# stm32f103.net
KiCad netlist of a schematic drawn in Altium Designer
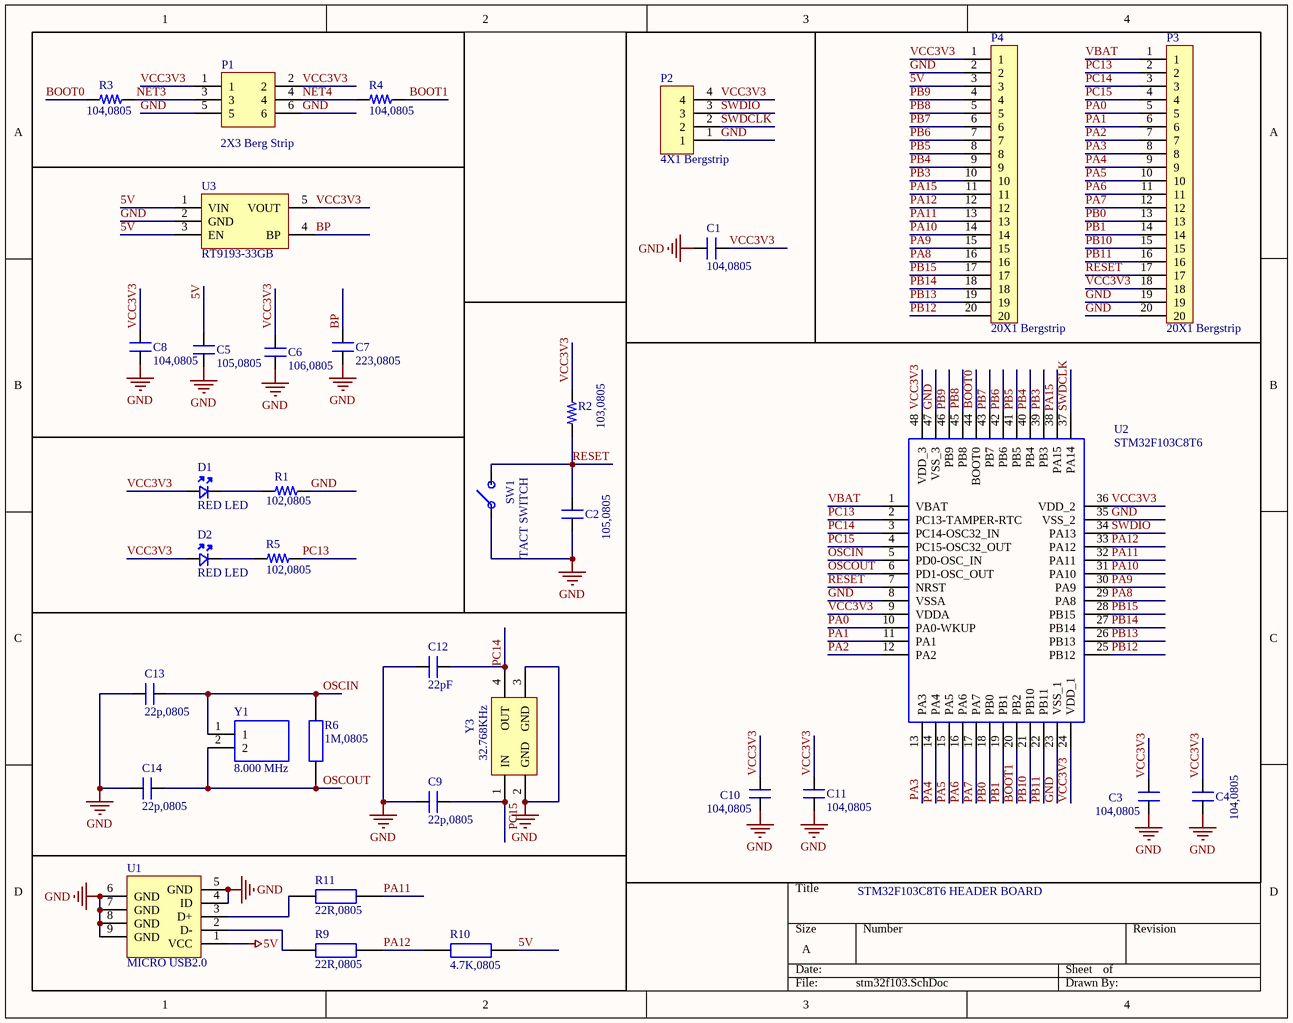
[diagram p0: stm32f103.SchDoc]

(export (version "E")
  (design (tool "Eeschema 10.0.6"))
  (components
    (comp (ref "C1")
      (value "104,0805")
      (footprint "CAP_0805")
      (description "0.1µF ±5% 50V Ceramic Capacitor X7R 0805 (2012 Metric)")
      (fields
        (field (name "MANUFACTURER") "KEMET")
        (field (name "MANUFACTURING PART NUMBER") "C0805C104J5RACTU")
      )
      (libsource (lib "STM_SCH_LIB") (part "CAP_0.1uF-50V-5%-0805"))
    )
    (comp (ref "C2")
      (value "105,0805")
      (footprint "CAP_0805")
      (description "1µF ±5% 50V Ceramic Capacitor X7R 0805 (2012 Metric)")
      (fields
        (field (name "MANUFACTURER") "Yageo")
        (field (name "MANUFACTURING PART NUMBER") "CC0805JKX7R9BB105")
      )
      (libsource (lib "STM_SCH_LIB") (part "CAP_1uF-50V-5%-0805"))
    )
    (comp (ref "C3")
      (value "104,0805")
      (footprint "CAP_0805")
      (description "0.1µF ±5% 50V Ceramic Capacitor X7R 0805 (2012 Metric)")
      (fields
        (field (name "MANUFACTURER") "KEMET")
        (field (name "MANUFACTURING PART NUMBER") "C0805C104J5RACTU")
      )
      (libsource (lib "STM_SCH_LIB") (part "CAP_0.1uF-50V-5%-0805"))
    )
    (comp (ref "C4")
      (value "104,0805")
      (footprint "CAP_0805")
      (description "0.1µF ±5% 50V Ceramic Capacitor X7R 0805 (2012 Metric)")
      (fields
        (field (name "MANUFACTURER") "KEMET")
        (field (name "MANUFACTURING PART NUMBER") "C0805C104J5RACTU")
      )
      (libsource (lib "STM_SCH_LIB") (part "CAP_0.1uF-50V-5%-0805"))
    )
    (comp (ref "C5")
      (value "105,0805")
      (footprint "CAP_0805")
      (description "1µF ±5% 50V Ceramic Capacitor X7R 0805 (2012 Metric)")
      (fields
        (field (name "MANUFACTURER") "Yageo")
        (field (name "MANUFACTURING PART NUMBER") "CC0805JKX7R9BB105")
      )
      (libsource (lib "STM_SCH_LIB") (part "CAP_1uF-50V-5%-0805"))
    )
    (comp (ref "C6")
      (value "106,0805")
      (footprint "CAP_0805")
      (description "10µF ±5% 50V Ceramic Capacitor X7R 0805 (2012 Metric)")
      (fields
        (field (name "MANUFACTURER") "Yageo")
        (field (name "MANUFACTURING PART NUMBER") "CC0805JKX7R9BB105")
      )
      (libsource (lib "STM_SCH_LIB") (part "CAP_1uF-50V-5%-0805"))
    )
    (comp (ref "C7")
      (value "223,0805")
      (footprint "CAP_0805")
      (description "0.1µF ±5% 50V Ceramic Capacitor X7R 0805 (2012 Metric)")
      (fields
        (field (name "MANUFACTURER") "KEMET")
        (field (name "MANUFACTURING PART NUMBER") "C0805C104J5RACTU")
      )
      (libsource (lib "STM_SCH_LIB") (part "CAP_0.1uF-50V-5%-0805"))
    )
    (comp (ref "C8")
      (value "104,0805")
      (footprint "CAP_0805")
      (description "0.1µF ±5% 50V Ceramic Capacitor X7R 0805 (2012 Metric)")
      (fields
        (field (name "MANUFACTURER") "KEMET")
        (field (name "MANUFACTURING PART NUMBER") "C0805C104J5RACTU")
      )
      (libsource (lib "STM_SCH_LIB") (part "CAP_0.1uF-50V-5%-0805"))
    )
    (comp (ref "C9")
      (value "22p,0805")
      (footprint "CAP_0805")
      (description "22pF ±5% 50V Ceramic Capacitor C0G, NP0 0805 (2012 Metric)")
      (fields
        (field (name "MANUFACTURER") "KEMET")
        (field (name "MANUFACTURER PART NUMBER") "C0805C220J5GACTU")
      )
      (libsource (lib "STM_SCH_LIB") (part "CAP_22pF-50V-5%-0805"))
    )
    (comp (ref "C10")
      (value "104,0805")
      (footprint "CAP_0805")
      (description "0.1µF ±5% 50V Ceramic Capacitor X7R 0805 (2012 Metric)")
      (fields
        (field (name "MANUFACTURER") "KEMET")
        (field (name "MANUFACTURING PART NUMBER") "C0805C104J5RACTU")
      )
      (libsource (lib "STM_SCH_LIB") (part "CAP_0.1uF-50V-5%-0805"))
    )
    (comp (ref "C11")
      (value "104,0805")
      (footprint "CAP_0805")
      (description "0.1µF ±5% 50V Ceramic Capacitor X7R 0805 (2012 Metric)")
      (fields
        (field (name "MANUFACTURER") "KEMET")
        (field (name "MANUFACTURING PART NUMBER") "C0805C104J5RACTU")
      )
      (libsource (lib "STM_SCH_LIB") (part "CAP_0.1uF-50V-5%-0805"))
    )
    (comp (ref "C12")
      (value "22pF")
      (footprint "CAP_0805")
      (description "22pF ±5% 50V Ceramic Capacitor C0G, NP0 0805 (2012 Metric)")
      (fields
        (field (name "MANUFACTURER") "KEMET")
        (field (name "MANUFACTURER PART NUMBER") "C0805C220J5GACTU")
      )
      (libsource (lib "STM_SCH_LIB") (part "CAP_22pF-50V-5%-0805"))
    )
    (comp (ref "C13")
      (value "22p,0805")
      (footprint "CAP_0805")
      (description "22pF ±5% 50V Ceramic Capacitor C0G, NP0 0805 (2012 Metric)")
      (fields
        (field (name "MANUFACTURER") "KEMET")
        (field (name "MANUFACTURER PART NUMBER") "C0805C220J5GACTU")
      )
      (libsource (lib "STM_SCH_LIB") (part "CAP_22pF-50V-5%-0805"))
    )
    (comp (ref "C14")
      (value "22p,0805")
      (footprint "CAP_0805")
      (description "22pF ±5% 50V Ceramic Capacitor C0G, NP0 0805 (2012 Metric)")
      (fields
        (field (name "MANUFACTURER") "KEMET")
        (field (name "MANUFACTURER PART NUMBER") "C0805C220J5GACTU")
      )
      (libsource (lib "STM_SCH_LIB") (part "CAP_22pF-50V-5%-0805"))
    )
    (comp (ref "D1")
      (value "RED LED")
      (footprint "LED_0805")
      (description "Red 621nm LED Indication - Discrete 2V 0805 (2012 Metric)")
      (fields
        (field (name "MANUFACTURER") "Lite-On Inc.")
        (field (name "MANUFACTURER PART NUMBER") "LTST-C170EKT")
      )
      (libsource (lib "STM_SCH_LIB") (part "LED-RED_10mA-0805"))
    )
    (comp (ref "D2")
      (value "RED LED")
      (footprint "LED_0805")
      (description "Red 621nm LED Indication - Discrete 2V 0805 (2012 Metric)")
      (fields
        (field (name "MANUFACTURER") "Lite-On Inc.")
        (field (name "MANUFACTURER PART NUMBER") "LTST-C170EKT")
      )
      (libsource (lib "STM_SCH_LIB") (part "LED-RED_10mA-0805"))
    )
    (comp (ref "P1")
      (value "2X3 Berg Strip")
      (footprint "CON6_100_59D78_TH_ST_Duplicate")
      (description "6 pin, 2 row, 2.54mm pitch bergstrip")
      (fields (field (name "MANUFACTURER") "NA"))
      (libsource (lib "STM_SCH_LIB") (part "CON-BS-PLG_2X3-100-TH-ST"))
    )
    (comp (ref "P2")
      (value "4X1 Bergstrip")
      (footprint "CON4_100_40D72_TH_ST_MALE")
      (description "4 pin, 1 row, 2.54mm pitch bergstrip")
      (fields (field (name "MANUFACTURER") "NA"))
      (libsource (lib "STM_SCH_LIB") (part "CON-BS-PLG_4X1-100-TH-ST"))
    )
    (comp (ref "P3")
      (value "20X1 Bergstrip")
      (footprint "CON20_100_40D72_TH_ST")
      (description "20 pin, 1 row, 2.54mm pitch bergstrip")
      (fields (field (name "MANUFACTURER") "NA"))
      (libsource (lib "STM_SCH_LIB") (part "CON-BS-PLG_20X1-100-TH-ST"))
    )
    (comp (ref "P4")
      (value "20X1 Bergstrip")
      (footprint "CON20_100_40D72_TH_ST")
      (description "20 pin, 1 row, 2.54mm pitch bergstrip")
      (fields (field (name "MANUFACTURER") "NA"))
      (libsource (lib "STM_SCH_LIB") (part "CON-BS-PLG_20X1-100-TH-ST"))
    )
    (comp (ref "R1")
      (value "102,0805")
      (footprint "RES_0805")
      (description "1 kOhms ±1% 0.125W, 1/8W Chip Resistor 0805 (2012 Metric) Moisture Resistant Thick Film")
      (fields (field (name "MANUFACTURER") "垈㎵á") (field (name "MANUFACTURER PART NUMBER") "RC0805FR-071KL"))
      (libsource (lib "STM_SCH_LIB") (part "RES_1K-0.125W-1%-0805"))
    )
    (comp (ref "R2")
      (value "103,0805")
      (footprint "RES_0805")
      (description "10 kOhms ±1% 0.125W, 1/8W Chip Resistor 0805 (2012 Metric) Moisture Resistant Thick Film")
      (fields
        (field (name "MANUFACTURER") "Yageo")
        (field (name "MANUFACTURING PART NUMBER") "RC0805FR-0710KL")
      )
      (libsource (lib "STM_SCH_LIB") (part "RES_10K-0.125W-1%-0805"))
    )
    (comp (ref "R3")
      (value "104,0805")
      (footprint "RES_0805")
      (description "10 kOhms ±1% 0.125W, 1/8W Chip Resistor 0805 (2012 Metric) Moisture Resistant Thick Film")
      (fields
        (field (name "MANUFACTURER") "Yageo")
        (field (name "MANUFACTURING PART NUMBER") "RC0805FR-0710KL")
      )
      (libsource (lib "STM_SCH_LIB") (part "RES_10K-0.125W-1%-0805"))
    )
    (comp (ref "R4")
      (value "104,0805")
      (footprint "RES_0805")
      (description "10 kOhms ±1% 0.125W, 1/8W Chip Resistor 0805 (2012 Metric) Moisture Resistant Thick Film")
      (fields
        (field (name "MANUFACTURER") "Yageo")
        (field (name "MANUFACTURING PART NUMBER") "RC0805FR-0710KL")
      )
      (libsource (lib "STM_SCH_LIB") (part "RES_10K-0.125W-1%-0805"))
    )
    (comp (ref "R5")
      (value "102,0805")
      (footprint "RES_0805")
      (description "1 kOhms ±1% 0.125W, 1/8W Chip Resistor 0805 (2012 Metric) Moisture Resistant Thick Film")
      (fields (field (name "MANUFACTURER") "垈㎵á") (field (name "MANUFACTURER PART NUMBER") "RC0805FR-071KL"))
      (libsource (lib "STM_SCH_LIB") (part "RES_1K-0.125W-1%-0805"))
    )
    (comp (ref "R6")
      (value "1M,0805")
      (footprint "RESC2013X65N")
      (description "TE Connectivity CRGS Series Thick Film Anti-surge Resistor 0805 Case 1M +/-5% 0.5W +/-100ppm/C")
      (fields
        (field (name "MANUFACTURER_PART_NUMBER") "CRGS0805J1M0")
        (field (name "RS PART NUMBER") "9059767")
      )
      (libsource (lib "Res_1M_0805") (part "CRGS0805J1M0"))
    )
    (comp (ref "R9")
      (value "22R,0805")
      (footprint "RESC2013X65N")
      (description "TE Connectivity Thick Film Surface Mount Fixed Resistor 0805 Case 22 +/-5% 0.33W +/-200ppm/C")
      (fields
        (field (name "MANUFACTURER_PART_NUMBER") "CRGH0805J22R")
        (field (name "MOUSER PART NUMBER") "279-CRGH0805J22R")
      )
      (libsource (lib "Res_22R_0805") (part "CRGH0805J22R"))
    )
    (comp (ref "R10")
      (value "4.7K,0805")
      (footprint "RESC2013X65N")
      (description "RESISTOR, 0805 4.7K Ohm +/-5% 0.125 W")
      (fields
        (field (name "MANUFACTURER_PART_NUMBER") "ERJ-6GEYJ472V")
        (field (name "MOUSER PART NUMBER") "667-ERJ-6GEYJ472V")
      )
      (libsource (lib "Res_4.7_0805") (part "ERJ-6GEYJ472V"))
    )
    (comp (ref "R11")
      (value "22R,0805")
      (footprint "RESC2013X65N")
      (description "TE Connectivity Thick Film Surface Mount Fixed Resistor 0805 Case 22 +/-5% 0.33W +/-200ppm/C")
      (fields
        (field (name "MANUFACTURER_PART_NUMBER") "CRGH0805J22R")
        (field (name "MOUSER PART NUMBER") "279-CRGH0805J22R")
      )
      (libsource (lib "Res_22R_0805") (part "CRGH0805J22R"))
    )
    (comp (ref "SW1")
      (value "TACT SWITCH")
      (footprint "SW_342_SMD")
      (description "Tactile Switch SPST-NO Top Actuated Surface Mount")
      (fields (field (name "MANUFACTURER") "C&K") (field (name "MANUFACTURING PART NUMBER") "KSR223GLFG"))
      (libsource (lib "STM_SCH_LIB") (part "SW_KSR223GLFG-SMD"))
    )
    (comp (ref "U1")
      (value "MICRO USB2.0")
      (footprint "CON_10118192-0001LF_SMD")
      (description "USB - micro B USB 2.0 Receptacle Connector 5 Position Surface Mount, Right Angle")
      (fields
        (field (name "MANUFACTURER") "Amphenol ICC (FCI)")
        (field (name "MANUFACTURING PART NUMBER") "10118192-0002LF")
      )
      (libsource (lib "STM_SCH_LIB") (part "CON-USB_10118192-0002LF-SMD"))
    )
    (comp (ref "U2")
      (value "STM32F103C8T6")
      (footprint "QFP50P900X900X160-48N")
      (fields
        (field (name "MOUSER PART NUMBER") "511-STM32F103C8T6")
        (field (name "RS PART NUMBER") "0402279P")
      )
      (libsource (lib "IC_STM32F103C8T6") (part "STM32F103C8T6"))
    )
    (comp (ref "U3")
      (value "RT9193-33GB")
      (footprint "SOT23-5")
      (description "Linear Voltage Regulator IC 1 Output 300mA SOT-23-5")
      (fields (field (name "MANUFACTURER") "Richtek USA Inc."))
      (libsource (lib "STM_SCH_LIB") (part "REG_3.3V-5.5V-0.3A-SOT-23-5"))
    )
    (comp (ref "Y1")
      (value "8.000 MHz")
      (footprint "HC-49S_1")
      (description "TXC - 9B-16.000MEEJ-B - XTAL, 16.000MHZ, 18PF, HC-49S")
      (fields
        (field (name "MANUFACTURER_PART_NUMBER") "9B-16.000MEEJ-B")
        (field (name "MOUSER PART NUMBER") "717-9B-16.000MEEJ-B")
      )
      (libsource (lib "16 MHz resonator") (part "9B-16.000MEEJ-B"))
    )
    (comp (ref "Y3")
      (value "32.768KHz")
      (footprint "XTAL_MC-405 32.7680K-G3")
      (description "Crystals SMD AT XTL MHZ +/-50PPM 12.5 PF 250 T/R")
      (fields
        (field (name "MANUFACTURER") "Epson")
        (field (name "MANUFACTURING PART NUMBER") "MC-405 32.7680K-G3: ROHS")
      )
      (libsource (lib "STM_SCH_LIB") (part "XTAL_32.768KHz-MC-405 32.7680K-G3"))
    )
  )
  (nets
    (net (code "1") (name "/BOOT0") (class "Default")
      (node (ref "R3") (pin "1") (pinfunction "1_1") (pintype "passive"))
      (node (ref "U2") (pin "44") (pinfunction "BOOT0_44") (pintype "passive"))
    )
    (net (code "2") (name "/BOOT1") (class "Default")
      (node (ref "R4") (pin "2") (pinfunction "2_2") (pintype "passive"))
      (node (ref "U2") (pin "20") (pinfunction "PB2_20") (pintype "passive"))
    )
    (net (code "3") (name "/BP") (class "Default")
      (node (ref "C7") (pin "2") (pinfunction "2_2") (pintype "passive"))
      (node (ref "U3") (pin "4") (pinfunction "BP_4") (pintype "passive"))
    )
    (net (code "4") (name "/NET3") (class "Default")
      (node (ref "P1") (pin "3") (pinfunction "3_3") (pintype "passive"))
      (node (ref "R3") (pin "2") (pinfunction "2_2") (pintype "passive"))
    )
    (net (code "5") (name "/NET4") (class "Default")
      (node (ref "P1") (pin "4") (pinfunction "4_4") (pintype "passive"))
      (node (ref "R4") (pin "1") (pinfunction "1_1") (pintype "passive"))
    )
    (net (code "6") (name "/OSCIN") (class "Default")
      (node (ref "C13") (pin "2") (pinfunction "2_2") (pintype "passive"))
      (node (ref "R6") (pin "2") (pinfunction "2_2") (pintype "passive"))
      (node (ref "U2") (pin "5") (pinfunction "PD0-OSC_IN_5") (pintype "passive"))
      (node (ref "Y1") (pin "1") (pinfunction "1_1") (pintype "passive"))
    )
    (net (code "7") (name "/OSCOUT") (class "Default")
      (node (ref "C14") (pin "2") (pinfunction "2_2") (pintype "passive"))
      (node (ref "R6") (pin "1") (pinfunction "1_1") (pintype "passive"))
      (node (ref "U2") (pin "6") (pinfunction "PD1-OSC_OUT_6") (pintype "passive"))
      (node (ref "Y1") (pin "2") (pinfunction "2_2") (pintype "passive"))
    )
    (net (code "8") (name "/PA0") (class "Default")
      (node (ref "P3") (pin "5") (pinfunction "5_5") (pintype "passive"))
      (node (ref "U2") (pin "10") (pinfunction "PA0-WKUP_10") (pintype "passive"))
    )
    (net (code "9") (name "/PA1") (class "Default")
      (node (ref "P3") (pin "6") (pinfunction "6_6") (pintype "passive"))
      (node (ref "U2") (pin "11") (pinfunction "PA1_11") (pintype "passive"))
    )
    (net (code "10") (name "/PA2") (class "Default")
      (node (ref "P3") (pin "7") (pinfunction "7_7") (pintype "passive"))
      (node (ref "U2") (pin "12") (pinfunction "PA2_12") (pintype "passive"))
    )
    (net (code "11") (name "/PA3") (class "Default")
      (node (ref "P3") (pin "8") (pinfunction "8_8") (pintype "passive"))
      (node (ref "U2") (pin "13") (pinfunction "PA3_13") (pintype "passive"))
    )
    (net (code "12") (name "/PA4") (class "Default")
      (node (ref "P3") (pin "9") (pinfunction "9_9") (pintype "passive"))
      (node (ref "U2") (pin "14") (pinfunction "PA4_14") (pintype "passive"))
    )
    (net (code "13") (name "/PA5") (class "Default")
      (node (ref "P3") (pin "10") (pinfunction "10_10") (pintype "passive"))
      (node (ref "U2") (pin "15") (pinfunction "PA5_15") (pintype "passive"))
    )
    (net (code "14") (name "/PA6") (class "Default")
      (node (ref "P3") (pin "11") (pinfunction "11_11") (pintype "passive"))
      (node (ref "U2") (pin "16") (pinfunction "PA6_16") (pintype "passive"))
    )
    (net (code "15") (name "/PA7") (class "Default")
      (node (ref "P3") (pin "12") (pinfunction "12_12") (pintype "passive"))
      (node (ref "U2") (pin "17") (pinfunction "PA7_17") (pintype "passive"))
    )
    (net (code "16") (name "/PA8") (class "Default")
      (node (ref "P4") (pin "16") (pinfunction "16_16") (pintype "passive"))
      (node (ref "U2") (pin "29") (pinfunction "PA8_29") (pintype "passive"))
    )
    (net (code "17") (name "/PA9") (class "Default")
      (node (ref "P4") (pin "15") (pinfunction "15_15") (pintype "passive"))
      (node (ref "U2") (pin "30") (pinfunction "PA9_30") (pintype "passive"))
    )
    (net (code "18") (name "/PA10") (class "Default")
      (node (ref "P4") (pin "14") (pinfunction "14_14") (pintype "passive"))
      (node (ref "U2") (pin "31") (pinfunction "PA10_31") (pintype "passive"))
    )
    (net (code "19") (name "/PA11") (class "Default")
      (node (ref "P4") (pin "13") (pinfunction "13_13") (pintype "passive"))
      (node (ref "R11") (pin "2") (pinfunction "2_2") (pintype "passive"))
      (node (ref "U2") (pin "32") (pinfunction "PA11_32") (pintype "passive"))
    )
    (net (code "20") (name "/PA12") (class "Default")
      (node (ref "P4") (pin "12") (pinfunction "12_12") (pintype "passive"))
      (node (ref "R10") (pin "1") (pinfunction "R1_1") (pintype "passive"))
      (node (ref "R9") (pin "2") (pinfunction "2_2") (pintype "passive"))
      (node (ref "U2") (pin "33") (pinfunction "PA12_33") (pintype "passive"))
    )
    (net (code "21") (name "/PA15") (class "Default")
      (node (ref "P4") (pin "11") (pinfunction "11_11") (pintype "passive"))
      (node (ref "U2") (pin "38") (pinfunction "PA15_38") (pintype "passive"))
    )
    (net (code "22") (name "/PB0") (class "Default")
      (node (ref "P3") (pin "13") (pinfunction "13_13") (pintype "passive"))
      (node (ref "U2") (pin "18") (pinfunction "PB0_18") (pintype "passive"))
    )
    (net (code "23") (name "/PB1") (class "Default")
      (node (ref "P3") (pin "14") (pinfunction "14_14") (pintype "passive"))
      (node (ref "U2") (pin "19") (pinfunction "PB1_19") (pintype "passive"))
    )
    (net (code "24") (name "/PB3") (class "Default")
      (node (ref "P4") (pin "10") (pinfunction "10_10") (pintype "passive"))
      (node (ref "U2") (pin "39") (pinfunction "PB3_39") (pintype "passive"))
    )
    (net (code "25") (name "/PB4") (class "Default")
      (node (ref "P4") (pin "9") (pinfunction "9_9") (pintype "passive"))
      (node (ref "U2") (pin "40") (pinfunction "PB4_40") (pintype "passive"))
    )
    (net (code "26") (name "/PB5") (class "Default")
      (node (ref "P4") (pin "8") (pinfunction "8_8") (pintype "passive"))
      (node (ref "U2") (pin "41") (pinfunction "PB5_41") (pintype "passive"))
    )
    (net (code "27") (name "/PB6") (class "Default")
      (node (ref "P4") (pin "7") (pinfunction "7_7") (pintype "passive"))
      (node (ref "U2") (pin "42") (pinfunction "PB6_42") (pintype "passive"))
    )
    (net (code "28") (name "/PB7") (class "Default")
      (node (ref "P4") (pin "6") (pinfunction "6_6") (pintype "passive"))
      (node (ref "U2") (pin "43") (pinfunction "PB7_43") (pintype "passive"))
    )
    (net (code "29") (name "/PB8") (class "Default")
      (node (ref "P4") (pin "5") (pinfunction "5_5") (pintype "passive"))
      (node (ref "U2") (pin "45") (pinfunction "PB8_45") (pintype "passive"))
    )
    (net (code "30") (name "/PB9") (class "Default")
      (node (ref "P4") (pin "4") (pinfunction "4_4") (pintype "passive"))
      (node (ref "U2") (pin "46") (pinfunction "PB9_46") (pintype "passive"))
    )
    (net (code "31") (name "/PB10") (class "Default")
      (node (ref "P3") (pin "15") (pinfunction "15_15") (pintype "passive"))
      (node (ref "U2") (pin "21") (pinfunction "PB10_21") (pintype "passive"))
    )
    (net (code "32") (name "/PB11") (class "Default")
      (node (ref "P3") (pin "16") (pinfunction "16_16") (pintype "passive"))
      (node (ref "U2") (pin "22") (pinfunction "PB11_22") (pintype "passive"))
    )
    (net (code "33") (name "/PB12") (class "Default")
      (node (ref "P4") (pin "20") (pinfunction "20_20") (pintype "passive"))
      (node (ref "U2") (pin "25") (pinfunction "PB12_25") (pintype "passive"))
    )
    (net (code "34") (name "/PB13") (class "Default")
      (node (ref "P4") (pin "19") (pinfunction "19_19") (pintype "passive"))
      (node (ref "U2") (pin "26") (pinfunction "PB13_26") (pintype "passive"))
    )
    (net (code "35") (name "/PB14") (class "Default")
      (node (ref "P4") (pin "18") (pinfunction "18_18") (pintype "passive"))
      (node (ref "U2") (pin "27") (pinfunction "PB14_27") (pintype "passive"))
    )
    (net (code "36") (name "/PB15") (class "Default")
      (node (ref "P4") (pin "17") (pinfunction "17_17") (pintype "passive"))
      (node (ref "U2") (pin "28") (pinfunction "PB15_28") (pintype "passive"))
    )
    (net (code "37") (name "/PC13") (class "Default")
      (node (ref "P3") (pin "2") (pinfunction "2_2") (pintype "passive"))
      (node (ref "R5") (pin "2") (pinfunction "2_2") (pintype "passive"))
      (node (ref "U2") (pin "2") (pinfunction "PC13-TAMPER-RTC_2") (pintype "passive"))
    )
    (net (code "38") (name "/PC14") (class "Default")
      (node (ref "C12") (pin "2") (pinfunction "2_2") (pintype "passive"))
      (node (ref "P3") (pin "3") (pinfunction "3_3") (pintype "passive"))
      (node (ref "U2") (pin "3") (pinfunction "PC14-OSC32_IN_3") (pintype "passive"))
      (node (ref "Y3") (pin "4") (pinfunction "OUT_4") (pintype "passive"))
    )
    (net (code "39") (name "/PC15") (class "Default")
      (node (ref "C9") (pin "2") (pinfunction "2_2") (pintype "passive"))
      (node (ref "P3") (pin "4") (pinfunction "4_4") (pintype "passive"))
      (node (ref "U2") (pin "4") (pinfunction "PC15-OSC32_OUT_4") (pintype "passive"))
      (node (ref "Y3") (pin "1") (pinfunction "IN_1") (pintype "passive"))
    )
    (net (code "40") (name "/RESET") (class "Default")
      (node (ref "C2") (pin "2") (pinfunction "2_2") (pintype "passive"))
      (node (ref "P3") (pin "17") (pinfunction "17_17") (pintype "passive"))
      (node (ref "R2") (pin "1") (pinfunction "1_1") (pintype "passive"))
      (node (ref "SW1") (pin "2") (pinfunction "2_2") (pintype "passive"))
      (node (ref "U2") (pin "7") (pinfunction "NRST_7") (pintype "passive"))
    )
    (net (code "41") (name "/SWDCLK") (class "Default")
      (node (ref "P2") (pin "2") (pinfunction "2_2") (pintype "passive"))
      (node (ref "U2") (pin "37") (pinfunction "PA14_37") (pintype "passive"))
    )
    (net (code "42") (name "/SWDIO") (class "Default")
      (node (ref "P2") (pin "3") (pinfunction "3_3") (pintype "passive"))
      (node (ref "U2") (pin "34") (pinfunction "PA13_34") (pintype "passive"))
    )
    (net (code "43") (name "/VBAT") (class "Default")
      (node (ref "P3") (pin "1") (pinfunction "1_1") (pintype "passive"))
      (node (ref "U2") (pin "1") (pinfunction "VBAT_1") (pintype "passive"))
    )
    (net (code "44") (name "/VCC3V3") (class "Default")
      (node (ref "C1") (pin "2") (pinfunction "2_2") (pintype "passive"))
      (node (ref "C10") (pin "2") (pinfunction "2_2") (pintype "passive"))
      (node (ref "C11") (pin "2") (pinfunction "2_2") (pintype "passive"))
      (node (ref "C3") (pin "2") (pinfunction "2_2") (pintype "passive"))
      (node (ref "C4") (pin "2") (pinfunction "2_2") (pintype "passive"))
      (node (ref "C6") (pin "2") (pinfunction "2_2") (pintype "passive"))
      (node (ref "C8") (pin "2") (pinfunction "2_2") (pintype "passive"))
      (node (ref "D1") (pin "A") (pinfunction "A_A") (pintype "passive"))
      (node (ref "D2") (pin "A") (pinfunction "A_A") (pintype "passive"))
      (node (ref "P1") (pin "1") (pinfunction "1_1") (pintype "passive"))
      (node (ref "P1") (pin "2") (pinfunction "2_2") (pintype "passive"))
      (node (ref "P2") (pin "4") (pinfunction "4_4") (pintype "passive"))
      (node (ref "P3") (pin "18") (pinfunction "18_18") (pintype "passive"))
      (node (ref "P4") (pin "1") (pinfunction "1_1") (pintype "passive"))
      (node (ref "R2") (pin "2") (pinfunction "2_2") (pintype "passive"))
      (node (ref "U2") (pin "24") (pinfunction "VDD_1_24") (pintype "power_in"))
      (node (ref "U2") (pin "36") (pinfunction "VDD_2_36") (pintype "power_in"))
      (node (ref "U2") (pin "48") (pinfunction "VDD_3_48") (pintype "power_in"))
      (node (ref "U2") (pin "9") (pinfunction "VDDA_9") (pintype "power_in"))
      (node (ref "U3") (pin "5") (pinfunction "VOUT_5") (pintype "passive"))
    )
    (net (code "45") (name "5V") (class "Default")
      (node (ref "C5") (pin "2") (pinfunction "2_2") (pintype "passive"))
      (node (ref "P4") (pin "3") (pinfunction "3_3") (pintype "passive"))
      (node (ref "R10") (pin "2") (pinfunction "R2_2") (pintype "passive"))
      (node (ref "U1") (pin "1") (pinfunction "VCC_1") (pintype "passive"))
      (node (ref "U3") (pin "1") (pinfunction "VIN_1") (pintype "passive"))
      (node (ref "U3") (pin "3") (pinfunction "EN_3") (pintype "passive"))
    )
    (net (code "46") (name "GND") (class "Default")
      (node (ref "C1") (pin "1") (pinfunction "1_1") (pintype "passive"))
      (node (ref "C10") (pin "1") (pinfunction "1_1") (pintype "passive"))
      (node (ref "C11") (pin "1") (pinfunction "1_1") (pintype "passive"))
      (node (ref "C12") (pin "1") (pinfunction "1_1") (pintype "passive"))
      (node (ref "C13") (pin "1") (pinfunction "1_1") (pintype "passive"))
      (node (ref "C14") (pin "1") (pinfunction "1_1") (pintype "passive"))
      (node (ref "C2") (pin "1") (pinfunction "1_1") (pintype "passive"))
      (node (ref "C3") (pin "1") (pinfunction "1_1") (pintype "passive"))
      (node (ref "C4") (pin "1") (pinfunction "1_1") (pintype "passive"))
      (node (ref "C5") (pin "1") (pinfunction "1_1") (pintype "passive"))
      (node (ref "C6") (pin "1") (pinfunction "1_1") (pintype "passive"))
      (node (ref "C7") (pin "1") (pinfunction "1_1") (pintype "passive"))
      (node (ref "C8") (pin "1") (pinfunction "1_1") (pintype "passive"))
      (node (ref "C9") (pin "1") (pinfunction "1_1") (pintype "passive"))
      (node (ref "P1") (pin "5") (pinfunction "5_5") (pintype "passive"))
      (node (ref "P1") (pin "6") (pinfunction "6_6") (pintype "passive"))
      (node (ref "P2") (pin "1") (pinfunction "1_1") (pintype "passive"))
      (node (ref "P3") (pin "19") (pinfunction "19_19") (pintype "passive"))
      (node (ref "P3") (pin "20") (pinfunction "20_20") (pintype "passive"))
      (node (ref "P4") (pin "2") (pinfunction "2_2") (pintype "passive"))
      (node (ref "R1") (pin "2") (pinfunction "2_2") (pintype "passive"))
      (node (ref "SW1") (pin "1") (pinfunction "1_1") (pintype "passive"))
      (node (ref "U1") (pin "4") (pinfunction "ID_4") (pintype "passive"))
      (node (ref "U1") (pin "5") (pinfunction "GND_5") (pintype "passive"))
      (node (ref "U1") (pin "6") (pinfunction "GND_6") (pintype "passive"))
      (node (ref "U1") (pin "7") (pinfunction "GND_7") (pintype "passive"))
      (node (ref "U1") (pin "8") (pinfunction "GND_8") (pintype "passive"))
      (node (ref "U1") (pin "9") (pinfunction "GND_9") (pintype "passive"))
      (node (ref "U2") (pin "23") (pinfunction "VSS_1_23") (pintype "passive"))
      (node (ref "U2") (pin "35") (pinfunction "VSS_2_35") (pintype "passive"))
      (node (ref "U2") (pin "47") (pinfunction "VSS_3_47") (pintype "passive"))
      (node (ref "U2") (pin "8") (pinfunction "VSSA_8") (pintype "passive"))
      (node (ref "U3") (pin "2") (pinfunction "GND_2") (pintype "passive"))
      (node (ref "Y3") (pin "2") (pinfunction "GND_2") (pintype "passive"))
      (node (ref "Y3") (pin "3") (pinfunction "GND_3") (pintype "passive"))
    )
    (net (code "47") (name "Net-(D1-PadK)") (class "Default")
      (node (ref "D1") (pin "K") (pinfunction "K_K") (pintype "passive"))
      (node (ref "R1") (pin "1") (pinfunction "1_1") (pintype "passive"))
    )
    (net (code "48") (name "Net-(D2-PadK)") (class "Default")
      (node (ref "D2") (pin "K") (pinfunction "K_K") (pintype "passive"))
      (node (ref "R5") (pin "1") (pinfunction "1_1") (pintype "passive"))
    )
    (net (code "49") (name "Net-(U1-D+)") (class "Default")
      (node (ref "R11") (pin "1") (pinfunction "1_1") (pintype "passive"))
      (node (ref "U1") (pin "3") (pinfunction "D+_3") (pintype "passive"))
    )
    (net (code "50") (name "Net-(U1-D-)") (class "Default")
      (node (ref "R9") (pin "1") (pinfunction "1_1") (pintype "passive"))
      (node (ref "U1") (pin "2") (pinfunction "D-_2") (pintype "passive"))
    )
  )
)
